# Sheet1.net
KiCad netlist of a schematic drawn in Altium Designer
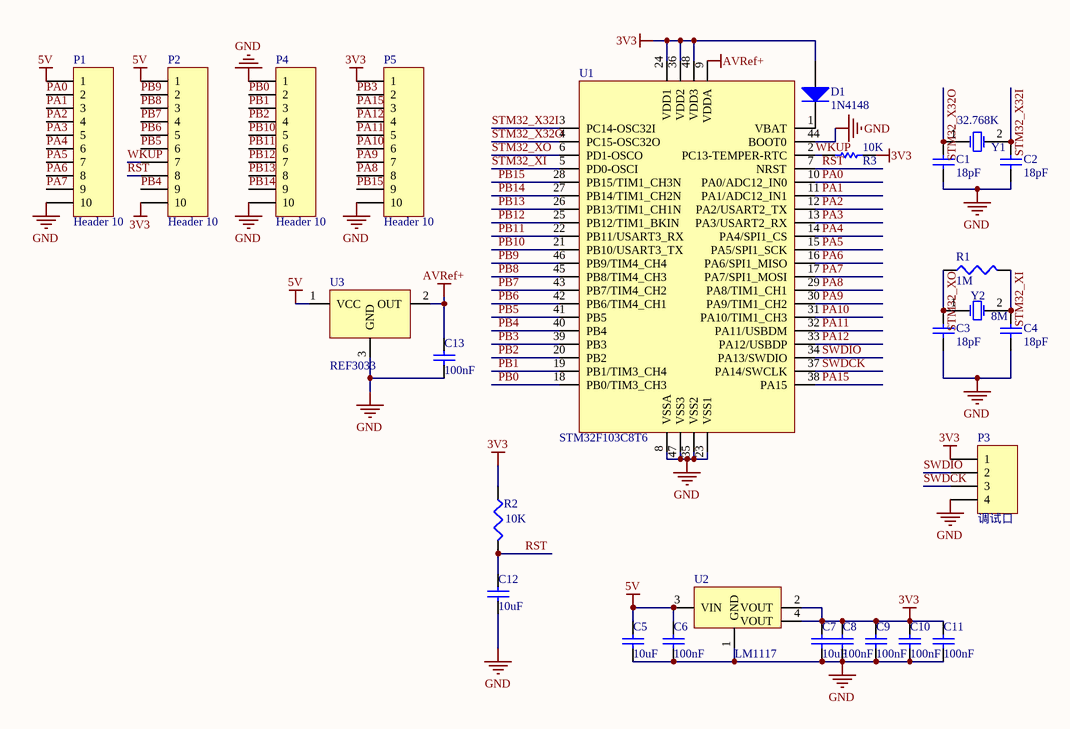
[diagram p0: Sheet1.SchDoc]

(export (version "E")
  (design (tool "Eeschema 10.0.6"))
  (components
    (comp (ref "C1")
      (value "18pF")
      (footprint "6-0805_N")
      (description "Capacitor")
      (fields (field (name "Comment") "Cap") (field (name "PUBLISHER") "Altium Limited"))
      (libsource (lib "Miscellaneous Devices") (part "Cap"))
    )
    (comp (ref "C2")
      (value "18pF")
      (footprint "6-0805_N")
      (description "Capacitor")
      (fields (field (name "Comment") "Cap") (field (name "PUBLISHER") "Altium Limited"))
      (libsource (lib "Miscellaneous Devices") (part "Cap"))
    )
    (comp (ref "C3")
      (value "18pF")
      (footprint "6-0805_N")
      (description "Capacitor")
      (fields (field (name "Comment") "Cap") (field (name "PUBLISHER") "Altium Limited"))
      (libsource (lib "Miscellaneous Devices") (part "Cap"))
    )
    (comp (ref "C4")
      (value "18pF")
      (footprint "6-0805_N")
      (description "Capacitor")
      (fields (field (name "Comment") "Cap") (field (name "PUBLISHER") "Altium Limited"))
      (libsource (lib "Miscellaneous Devices") (part "Cap"))
    )
    (comp (ref "C5")
      (value "10uF")
      (footprint "6-0805_N")
      (description "Capacitor")
      (fields (field (name "Comment") "Cap") (field (name "PUBLISHER") "Altium Limited"))
      (libsource (lib "Miscellaneous Devices") (part "Cap"))
    )
    (comp (ref "C6")
      (value "100nF")
      (footprint "6-0805_N")
      (description "Capacitor")
      (fields (field (name "Comment") "Cap") (field (name "PUBLISHER") "Altium Limited"))
      (libsource (lib "Miscellaneous Devices") (part "Cap"))
    )
    (comp (ref "C7")
      (value "10uF")
      (footprint "6-0805_N")
      (description "Capacitor")
      (fields (field (name "Comment") "Cap") (field (name "PUBLISHER") "Altium Limited"))
      (libsource (lib "Miscellaneous Devices") (part "Cap"))
    )
    (comp (ref "C8")
      (value "100nF")
      (footprint "6-0805_N")
      (description "Capacitor")
      (fields (field (name "Comment") "Cap") (field (name "PUBLISHER") "Altium Limited"))
      (libsource (lib "Miscellaneous Devices") (part "Cap"))
    )
    (comp (ref "C9")
      (value "100nF")
      (footprint "6-0805_N")
      (description "Capacitor")
      (fields (field (name "Comment") "Cap") (field (name "PUBLISHER") "Altium Limited"))
      (libsource (lib "Miscellaneous Devices") (part "Cap"))
    )
    (comp (ref "C10")
      (value "100nF")
      (footprint "6-0805_N")
      (description "Capacitor")
      (fields (field (name "Comment") "Cap") (field (name "PUBLISHER") "Altium Limited"))
      (libsource (lib "Miscellaneous Devices") (part "Cap"))
    )
    (comp (ref "C11")
      (value "100nF")
      (footprint "6-0805_N")
      (description "Capacitor")
      (fields (field (name "PUBLISHER") "Altium Limited"))
      (libsource (lib "Miscellaneous Devices") (part "Cap"))
    )
    (comp (ref "C12")
      (value "10uF")
      (footprint "6-0805_N")
      (description "Capacitor")
      (fields (field (name "Comment") "Cap") (field (name "PUBLISHER") "Altium Limited"))
      (libsource (lib "Miscellaneous Devices") (part "Cap"))
    )
    (comp (ref "C13")
      (value "100nF")
      (footprint "6-0805_N")
      (description "Capacitor")
      (fields (field (name "PUBLISHER") "Altium Limited"))
      (libsource (lib "Miscellaneous Devices") (part "Cap"))
    )
    (comp (ref "D1")
      (value "1N4148")
      (footprint "C1206")
      (description "High Conductance Fast Diode")
      (fields (field (name "PUBLISHER") "Altium Limited"))
      (libsource (lib "Miscellaneous Devices") (part "Diode 1N4148"))
    )
    (comp (ref "P1")
      (value "Header 10")
      (footprint "HDR1X10")
      (description "Header, 10-Pin")
      (fields (field (name "PUBLISHER") "Altium Limited"))
      (libsource (lib "Miscellaneous Connectors") (part "Header 10"))
    )
    (comp (ref "P2")
      (value "Header 10")
      (footprint "HDR1X10")
      (description "Header, 10-Pin")
      (fields (field (name "PUBLISHER") "Altium Limited"))
      (libsource (lib "Miscellaneous Connectors") (part "Header 10"))
    )
    (comp (ref "P3")
      (value "调试口")
      (footprint "HDR1X4")
      (description "Header, 4-Pin")
      (fields (field (name "PUBLISHER") "Altium Limited"))
      (libsource (lib "Miscellaneous Connectors") (part "Header 4"))
    )
    (comp (ref "P4")
      (value "Header 10")
      (footprint "HDR1X10")
      (description "Header, 10-Pin")
      (fields (field (name "PUBLISHER") "Altium Limited"))
      (libsource (lib "Miscellaneous Connectors") (part "Header 10"))
    )
    (comp (ref "P5")
      (value "Header 10")
      (footprint "HDR1X10")
      (description "Header, 10-Pin")
      (fields (field (name "PUBLISHER") "Altium Limited"))
      (libsource (lib "Miscellaneous Connectors") (part "Header 10"))
    )
    (comp (ref "R1")
      (value "1M")
      (footprint "6-0805_N")
      (description "Resistor")
      (fields (field (name "Comment") "Res3") (field (name "PUBLISHER") "Altium Limited"))
      (libsource (lib "Miscellaneous Devices") (part "Res3"))
    )
    (comp (ref "R2")
      (value "10K")
      (footprint "6-0805_N")
      (description "Resistor")
      (fields (field (name "Comment") "Res3") (field (name "PUBLISHER") "Altium Limited"))
      (libsource (lib "Miscellaneous Devices") (part "Res3"))
    )
    (comp (ref "R3")
      (value "10K")
      (footprint "6-0805_N")
      (description "Resistor")
      (fields (field (name "Comment") "Res1") (field (name "PUBLISHER") "Altium Limited"))
      (libsource (lib "Miscellaneous Devices") (part "Res1"))
    )
    (comp (ref "U1")
      (value "STM32F103C8T6")
      (footprint "LQFP48-7x7")
      (libsource (lib "STM32") (part "STM32F103CxT6"))
    )
    (comp (ref "U2") (value "LM1117") (footprint "SOT223_N") (libsource (lib "PublicSch") (part "LM1117")))
    (comp (ref "U3") (value "REF3033") (footprint "SOT-23_N") (libsource (lib "PublicSch") (part "REF30xx")))
    (comp (ref "Y1")
      (value "32.768K")
      (footprint "XTAL-3215")
      (description "Crystal Oscillator")
      (fields (field (name "PUBLISHER") "Altium Limited"))
      (libsource (lib "Miscellaneous Devices") (part "XTAL"))
    )
    (comp (ref "Y2")
      (value "8M")
      (footprint "XTAL-5032")
      (description "Crystal Oscillator")
      (fields (field (name "PUBLISHER") "Altium Limited"))
      (libsource (lib "Miscellaneous Devices") (part "XTAL"))
    )
  )
  (nets
    (net (code "1") (name "/PA0") (class "Default")
      (node (ref "P1") (pin "2") (pinfunction "2_2") (pintype "passive"))
      (node (ref "U1") (pin "10") (pinfunction "PA0/ADC12_IN0_10") (pintype "passive"))
    )
    (net (code "2") (name "/PA1") (class "Default")
      (node (ref "P1") (pin "3") (pinfunction "3_3") (pintype "passive"))
      (node (ref "U1") (pin "11") (pinfunction "PA1/ADC12_IN1_11") (pintype "passive"))
    )
    (net (code "3") (name "/PA2") (class "Default")
      (node (ref "P1") (pin "4") (pinfunction "4_4") (pintype "passive"))
      (node (ref "U1") (pin "12") (pinfunction "PA2/USART2_TX_12") (pintype "passive"))
    )
    (net (code "4") (name "/PA3") (class "Default")
      (node (ref "P1") (pin "5") (pinfunction "5_5") (pintype "passive"))
      (node (ref "U1") (pin "13") (pinfunction "PA3/USART2_RX_13") (pintype "passive"))
    )
    (net (code "5") (name "/PA4") (class "Default")
      (node (ref "P1") (pin "6") (pinfunction "6_6") (pintype "passive"))
      (node (ref "U1") (pin "14") (pinfunction "PA4/SPI1_CS_14") (pintype "passive"))
    )
    (net (code "6") (name "/PA5") (class "Default")
      (node (ref "P1") (pin "7") (pinfunction "7_7") (pintype "passive"))
      (node (ref "U1") (pin "15") (pinfunction "PA5/SPI1_SCK_15") (pintype "passive"))
    )
    (net (code "7") (name "/PA6") (class "Default")
      (node (ref "P1") (pin "8") (pinfunction "8_8") (pintype "passive"))
      (node (ref "U1") (pin "16") (pinfunction "PA6/SPI1_MISO_16") (pintype "passive"))
    )
    (net (code "8") (name "/PA7") (class "Default")
      (node (ref "P1") (pin "9") (pinfunction "9_9") (pintype "passive"))
      (node (ref "U1") (pin "17") (pinfunction "PA7/SPI1_MOSI_17") (pintype "passive"))
    )
    (net (code "9") (name "/PA8") (class "Default")
      (node (ref "P5") (pin "8") (pinfunction "8_8") (pintype "passive"))
      (node (ref "U1") (pin "29") (pinfunction "PA8/TIM1_CH1_29") (pintype "passive"))
    )
    (net (code "10") (name "/PA9") (class "Default")
      (node (ref "P5") (pin "7") (pinfunction "7_7") (pintype "passive"))
      (node (ref "U1") (pin "30") (pinfunction "PA9/TIM1_CH2_30") (pintype "passive"))
    )
    (net (code "11") (name "/PA10") (class "Default")
      (node (ref "P5") (pin "6") (pinfunction "6_6") (pintype "passive"))
      (node (ref "U1") (pin "31") (pinfunction "PA10/TIM1_CH3_31") (pintype "passive"))
    )
    (net (code "12") (name "/PA11") (class "Default")
      (node (ref "P5") (pin "5") (pinfunction "5_5") (pintype "passive"))
      (node (ref "U1") (pin "32") (pinfunction "PA11/USBDM_32") (pintype "passive"))
    )
    (net (code "13") (name "/PA12") (class "Default")
      (node (ref "P5") (pin "4") (pinfunction "4_4") (pintype "passive"))
      (node (ref "U1") (pin "33") (pinfunction "PA12/USBDP_33") (pintype "passive"))
    )
    (net (code "14") (name "/PA15") (class "Default")
      (node (ref "P5") (pin "3") (pinfunction "3_3") (pintype "passive"))
      (node (ref "U1") (pin "38") (pinfunction "PA15_38") (pintype "passive"))
    )
    (net (code "15") (name "/PB0") (class "Default")
      (node (ref "P4") (pin "2") (pinfunction "2_2") (pintype "passive"))
      (node (ref "U1") (pin "18") (pinfunction "PB0/TIM3_CH3_18") (pintype "passive"))
    )
    (net (code "16") (name "/PB1") (class "Default")
      (node (ref "P4") (pin "3") (pinfunction "3_3") (pintype "passive"))
      (node (ref "U1") (pin "19") (pinfunction "PB1/TIM3_CH4_19") (pintype "passive"))
    )
    (net (code "17") (name "/PB2") (class "Default")
      (node (ref "P4") (pin "4") (pinfunction "4_4") (pintype "passive"))
      (node (ref "U1") (pin "20") (pinfunction "PB2_20") (pintype "passive"))
    )
    (net (code "18") (name "/PB3") (class "Default")
      (node (ref "P5") (pin "2") (pinfunction "2_2") (pintype "passive"))
      (node (ref "U1") (pin "39") (pinfunction "PB3_39") (pintype "passive"))
    )
    (net (code "19") (name "/PB4") (class "Default")
      (node (ref "P2") (pin "9") (pinfunction "9_9") (pintype "passive"))
      (node (ref "U1") (pin "40") (pinfunction "PB4_40") (pintype "passive"))
    )
    (net (code "20") (name "/PB5") (class "Default")
      (node (ref "P2") (pin "6") (pinfunction "6_6") (pintype "passive"))
      (node (ref "U1") (pin "41") (pinfunction "PB5_41") (pintype "passive"))
    )
    (net (code "21") (name "/PB6") (class "Default")
      (node (ref "P2") (pin "5") (pinfunction "5_5") (pintype "passive"))
      (node (ref "U1") (pin "42") (pinfunction "PB6/TIM4_CH1_42") (pintype "passive"))
    )
    (net (code "22") (name "/PB7") (class "Default")
      (node (ref "P2") (pin "4") (pinfunction "4_4") (pintype "passive"))
      (node (ref "U1") (pin "43") (pinfunction "PB7/TIM4_CH2_43") (pintype "passive"))
    )
    (net (code "23") (name "/PB8") (class "Default")
      (node (ref "P2") (pin "3") (pinfunction "3_3") (pintype "passive"))
      (node (ref "U1") (pin "45") (pinfunction "PB8/TIM4_CH3_45") (pintype "passive"))
    )
    (net (code "24") (name "/PB9") (class "Default")
      (node (ref "P2") (pin "2") (pinfunction "2_2") (pintype "passive"))
      (node (ref "U1") (pin "46") (pinfunction "PB9/TIM4_CH4_46") (pintype "passive"))
    )
    (net (code "25") (name "/PB10") (class "Default")
      (node (ref "P4") (pin "5") (pinfunction "5_5") (pintype "passive"))
      (node (ref "U1") (pin "21") (pinfunction "PB10/USART3_TX_21") (pintype "passive"))
    )
    (net (code "26") (name "/PB11") (class "Default")
      (node (ref "P4") (pin "6") (pinfunction "6_6") (pintype "passive"))
      (node (ref "U1") (pin "22") (pinfunction "PB11/USART3_RX_22") (pintype "passive"))
    )
    (net (code "27") (name "/PB12") (class "Default")
      (node (ref "P4") (pin "7") (pinfunction "7_7") (pintype "passive"))
      (node (ref "U1") (pin "25") (pinfunction "PB12/TIM1_BKIN_25") (pintype "passive"))
    )
    (net (code "28") (name "/PB13") (class "Default")
      (node (ref "P4") (pin "8") (pinfunction "8_8") (pintype "passive"))
      (node (ref "U1") (pin "26") (pinfunction "PB13/TIM1_CH1N_26") (pintype "passive"))
    )
    (net (code "29") (name "/PB14") (class "Default")
      (node (ref "P4") (pin "9") (pinfunction "9_9") (pintype "passive"))
      (node (ref "U1") (pin "27") (pinfunction "PB14/TIM1_CH2N_27") (pintype "passive"))
    )
    (net (code "30") (name "/PB15") (class "Default")
      (node (ref "P5") (pin "9") (pinfunction "9_9") (pintype "passive"))
      (node (ref "U1") (pin "28") (pinfunction "PB15/TIM1_CH3N_28") (pintype "passive"))
    )
    (net (code "31") (name "/RST") (class "Default")
      (node (ref "C12") (pin "2") (pinfunction "2_2") (pintype "passive"))
      (node (ref "P2") (pin "8") (pinfunction "8_8") (pintype "passive"))
      (node (ref "R2") (pin "2") (pinfunction "2_2") (pintype "passive"))
      (node (ref "U1") (pin "7") (pinfunction "NRST_7") (pintype "passive"))
    )
    (net (code "32") (name "/STM32_X32I") (class "Default")
      (node (ref "C2") (pin "1") (pinfunction "1_1") (pintype "passive"))
      (node (ref "U1") (pin "3") (pinfunction "PC14-OSC32I_3") (pintype "passive"))
      (node (ref "Y1") (pin "2") (pinfunction "OSC2_2") (pintype "passive"))
    )
    (net (code "33") (name "/STM32_X32O") (class "Default")
      (node (ref "C1") (pin "1") (pinfunction "1_1") (pintype "passive"))
      (node (ref "U1") (pin "4") (pinfunction "PC15-OSC32O_4") (pintype "passive"))
      (node (ref "Y1") (pin "1") (pinfunction "OSC1_1") (pintype "passive"))
    )
    (net (code "34") (name "/STM32_XI") (class "Default")
      (node (ref "C4") (pin "1") (pinfunction "1_1") (pintype "passive"))
      (node (ref "R1") (pin "2") (pinfunction "2_2") (pintype "passive"))
      (node (ref "U1") (pin "5") (pinfunction "PD0-OSCI_5") (pintype "passive"))
      (node (ref "Y2") (pin "2") (pinfunction "OSC2_2") (pintype "passive"))
    )
    (net (code "35") (name "/STM32_XO") (class "Default")
      (node (ref "C3") (pin "1") (pinfunction "1_1") (pintype "passive"))
      (node (ref "R1") (pin "1") (pinfunction "1_1") (pintype "passive"))
      (node (ref "U1") (pin "6") (pinfunction "PD1-OSCO_6") (pintype "passive"))
      (node (ref "Y2") (pin "1") (pinfunction "OSC1_1") (pintype "passive"))
    )
    (net (code "36") (name "/SWDCK") (class "Default")
      (node (ref "P3") (pin "3") (pinfunction "3_3") (pintype "passive"))
      (node (ref "U1") (pin "37") (pinfunction "PA14/SWCLK_37") (pintype "passive"))
    )
    (net (code "37") (name "/SWDIO") (class "Default")
      (node (ref "P3") (pin "2") (pinfunction "2_2") (pintype "passive"))
      (node (ref "U1") (pin "34") (pinfunction "PA13/SWDIO_34") (pintype "passive"))
    )
    (net (code "38") (name "/WKUP") (class "Default")
      (node (ref "P2") (pin "7") (pinfunction "7_7") (pintype "passive"))
      (node (ref "R3") (pin "1") (pinfunction "1_1") (pintype "passive"))
      (node (ref "U1") (pin "2") (pinfunction "PC13-TEMPER-RTC_2") (pintype "passive"))
    )
    (net (code "39") (name "3V3") (class "Default")
      (node (ref "C10") (pin "2") (pinfunction "2_2") (pintype "passive"))
      (node (ref "C11") (pin "2") (pinfunction "2_2") (pintype "passive"))
      (node (ref "C7") (pin "2") (pinfunction "2_2") (pintype "passive"))
      (node (ref "C8") (pin "2") (pinfunction "2_2") (pintype "passive"))
      (node (ref "C9") (pin "2") (pinfunction "2_2") (pintype "passive"))
      (node (ref "D1") (pin "1") (pinfunction "A_1") (pintype "passive"))
      (node (ref "P2") (pin "10") (pinfunction "10_10") (pintype "passive"))
      (node (ref "P3") (pin "1") (pinfunction "1_1") (pintype "passive"))
      (node (ref "P5") (pin "1") (pinfunction "1_1") (pintype "passive"))
      (node (ref "R2") (pin "1") (pinfunction "1_1") (pintype "passive"))
      (node (ref "R3") (pin "2") (pinfunction "2_2") (pintype "passive"))
      (node (ref "U1") (pin "24") (pinfunction "VDD1_24") (pintype "passive"))
      (node (ref "U1") (pin "36") (pinfunction "VDD2_36") (pintype "passive"))
      (node (ref "U1") (pin "48") (pinfunction "VDD3_48") (pintype "passive"))
      (node (ref "U2") (pin "2") (pinfunction "VOUT_2") (pintype "passive"))
      (node (ref "U2") (pin "4") (pinfunction "VOUT_4") (pintype "passive"))
    )
    (net (code "40") (name "5V") (class "Default")
      (node (ref "C5") (pin "2") (pinfunction "2_2") (pintype "passive"))
      (node (ref "C6") (pin "2") (pinfunction "2_2") (pintype "passive"))
      (node (ref "P1") (pin "1") (pinfunction "1_1") (pintype "passive"))
      (node (ref "P2") (pin "1") (pinfunction "1_1") (pintype "passive"))
      (node (ref "U2") (pin "3") (pinfunction "VIN_3") (pintype "passive"))
      (node (ref "U3") (pin "1") (pinfunction "VCC_1") (pintype "power_in"))
    )
    (net (code "41") (name "AVRef+") (class "Default")
      (node (ref "C13") (pin "2") (pinfunction "2_2") (pintype "passive"))
      (node (ref "U1") (pin "9") (pinfunction "VDDA_9") (pintype "passive"))
      (node (ref "U3") (pin "2") (pinfunction "OUT_2") (pintype "power_in"))
    )
    (net (code "42") (name "GND") (class "Default")
      (node (ref "C1") (pin "2") (pinfunction "2_2") (pintype "passive"))
      (node (ref "C10") (pin "1") (pinfunction "1_1") (pintype "passive"))
      (node (ref "C11") (pin "1") (pinfunction "1_1") (pintype "passive"))
      (node (ref "C12") (pin "1") (pinfunction "1_1") (pintype "passive"))
      (node (ref "C13") (pin "1") (pinfunction "1_1") (pintype "passive"))
      (node (ref "C2") (pin "2") (pinfunction "2_2") (pintype "passive"))
      (node (ref "C3") (pin "2") (pinfunction "2_2") (pintype "passive"))
      (node (ref "C4") (pin "2") (pinfunction "2_2") (pintype "passive"))
      (node (ref "C5") (pin "1") (pinfunction "1_1") (pintype "passive"))
      (node (ref "C6") (pin "1") (pinfunction "1_1") (pintype "passive"))
      (node (ref "C7") (pin "1") (pinfunction "1_1") (pintype "passive"))
      (node (ref "C8") (pin "1") (pinfunction "1_1") (pintype "passive"))
      (node (ref "C9") (pin "1") (pinfunction "1_1") (pintype "passive"))
      (node (ref "P1") (pin "10") (pinfunction "10_10") (pintype "passive"))
      (node (ref "P3") (pin "4") (pinfunction "4_4") (pintype "passive"))
      (node (ref "P4") (pin "1") (pinfunction "1_1") (pintype "passive"))
      (node (ref "P4") (pin "10") (pinfunction "10_10") (pintype "passive"))
      (node (ref "P5") (pin "10") (pinfunction "10_10") (pintype "passive"))
      (node (ref "U1") (pin "23") (pinfunction "VSS1_23") (pintype "passive"))
      (node (ref "U1") (pin "35") (pinfunction "VSS2_35") (pintype "passive"))
      (node (ref "U1") (pin "44") (pinfunction "BOOT0_44") (pintype "passive"))
      (node (ref "U1") (pin "47") (pinfunction "VSS3_47") (pintype "passive"))
      (node (ref "U1") (pin "8") (pinfunction "VSSA_8") (pintype "passive"))
      (node (ref "U2") (pin "1") (pinfunction "GND_1") (pintype "passive"))
      (node (ref "U3") (pin "3") (pinfunction "GND_3") (pintype "power_in"))
    )
    (net (code "43") (name "Net-(D1-K)") (class "Default")
      (node (ref "D1") (pin "2") (pinfunction "K_2") (pintype "passive"))
      (node (ref "U1") (pin "1") (pinfunction "VBAT_1") (pintype "passive"))
    )
  )
)
